# nonregulation-level-shifter-mk-2_0.net
KiCad netlist of a schematic drawn in EAGLE
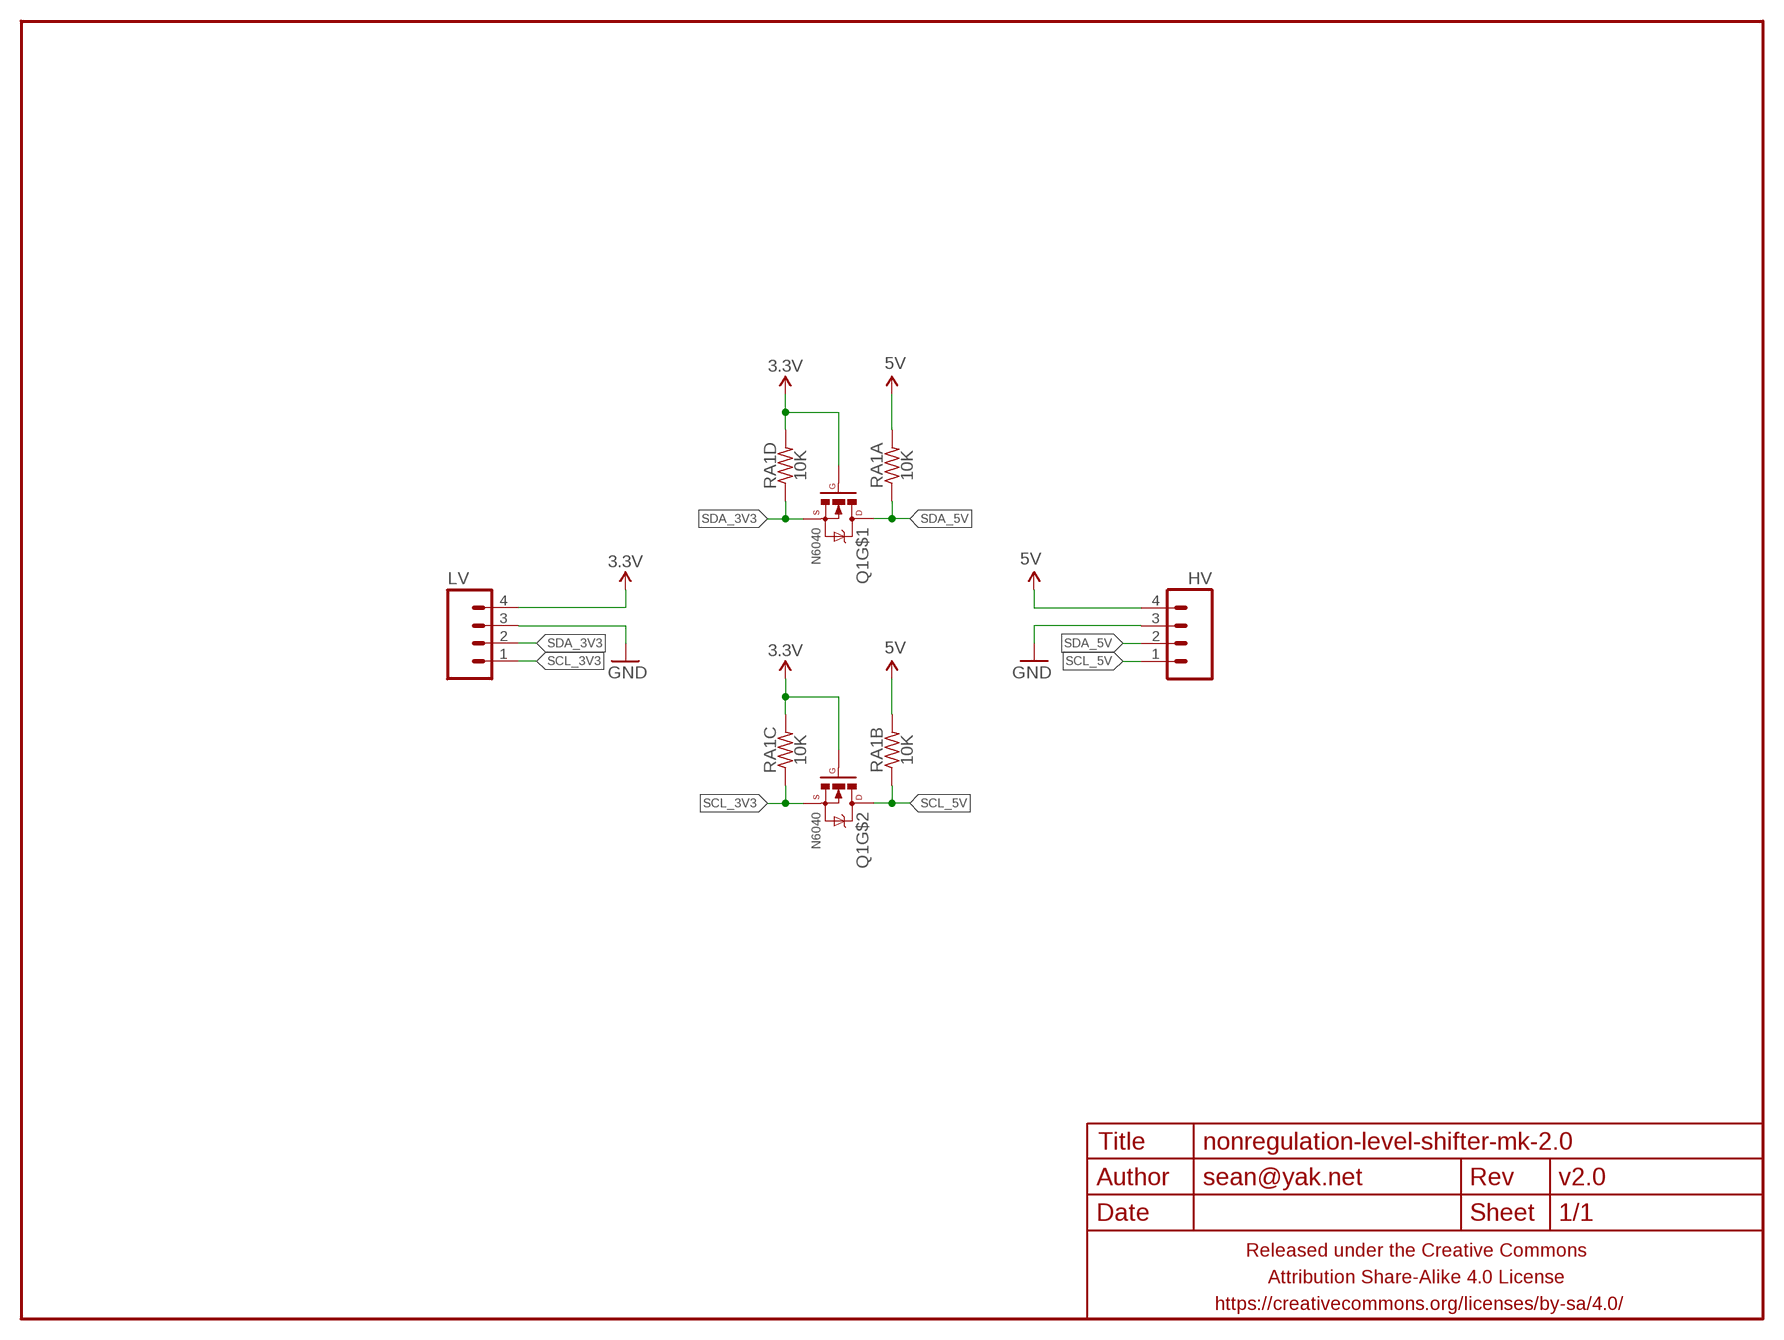
[diagram p0: schematic, sheet 1]

(export (version "E")
  (design (tool "Eeschema 10.0.6"))
  (components
    (comp (ref "FRAME1")
      (value "FRAME-LETTERNO_PACKAGE")
      (footprint "eagle-import:DUMMY")
      (fields (field (name "DESIGNER") "sean@yak.net") (field (name "VERSION") "v2.0"))
      (libsource (lib "eagle-import") (part "FRAME-LETTERNO_PACKAGE"))
    )
    (comp (ref "HV")
      (value "M04PTH-CENTERED")
      (footprint "eagle-import:1X04-PTH-VERT-CENTER")
      (libsource (lib "eagle-import") (part "M04PTH-CENTERED"))
    )
    (comp (ref "LV")
      (value "M04PTH-CENTERED")
      (footprint "eagle-import:1X04-PTH-VERT-CENTER")
      (libsource (lib "eagle-import") (part "M04PTH-CENTERED"))
    )
    (comp (ref "Q1")
      (value "N6040")
      (footprint "eagle-import:SO08")
      (libsource (lib "eagle-import") (part "MOSFET-NCHANNEL-DUALSOIC8"))
    )
    (comp (ref "RA1")
      (value "10K")
      (footprint "eagle-import:R1206-ARRAY-4")
      (libsource (lib "eagle-import") (part "RESISTOR-ARRAY-4YC164"))
    )
  )
  (nets
    (net (code "1") (name "3.3V") (class "Default")
      (node (ref "LV") (pin "4") (pinfunction "4_4") (pintype "passive"))
      (node (ref "Q1") (pin "2") (pinfunction "G_2") (pintype "passive"))
      (node (ref "Q1") (pin "4") (pinfunction "G_4") (pintype "passive"))
      (node (ref "RA1") (pin "C2") (pinfunction "2_C2") (pintype "passive"))
      (node (ref "RA1") (pin "D2") (pinfunction "2_D2") (pintype "passive"))
    )
    (net (code "2") (name "5V") (class "Default")
      (node (ref "HV") (pin "4") (pinfunction "4_4") (pintype "passive"))
      (node (ref "RA1") (pin "A2") (pinfunction "2_A2") (pintype "passive"))
      (node (ref "RA1") (pin "B2") (pinfunction "2_B2") (pintype "passive"))
    )
    (net (code "3") (name "GND") (class "Default")
      (node (ref "HV") (pin "3") (pinfunction "3_3") (pintype "passive"))
      (node (ref "LV") (pin "3") (pinfunction "3_3") (pintype "passive"))
    )
    (net (code "4") (name "SCL_3V3") (class "Default")
      (node (ref "LV") (pin "1") (pinfunction "1_1") (pintype "passive"))
      (node (ref "Q1") (pin "3") (pinfunction "S_3") (pintype "passive"))
      (node (ref "RA1") (pin "C1") (pinfunction "1_C1") (pintype "passive"))
    )
    (net (code "5") (name "SCL_5V") (class "Default")
      (node (ref "HV") (pin "1") (pinfunction "1_1") (pintype "passive"))
      (node (ref "Q1") (pin "5") (pinfunction "D_5") (pintype "passive"))
      (node (ref "Q1") (pin "6") (pinfunction "D_6") (pintype "passive"))
      (node (ref "RA1") (pin "B1") (pinfunction "1_B1") (pintype "passive"))
    )
    (net (code "6") (name "SDA_3V3") (class "Default")
      (node (ref "LV") (pin "2") (pinfunction "2_2") (pintype "passive"))
      (node (ref "Q1") (pin "1") (pinfunction "S_1") (pintype "passive"))
      (node (ref "RA1") (pin "D1") (pinfunction "1_D1") (pintype "passive"))
    )
    (net (code "7") (name "SDA_5V") (class "Default")
      (node (ref "HV") (pin "2") (pinfunction "2_2") (pintype "passive"))
      (node (ref "Q1") (pin "7") (pinfunction "D_7") (pintype "passive"))
      (node (ref "Q1") (pin "8") (pinfunction "D_8") (pintype "passive"))
      (node (ref "RA1") (pin "A1") (pinfunction "1_A1") (pintype "passive"))
    )
  )
)
